# RollerControllerUSB.net
KiCad netlist of a schematic drawn in EAGLE
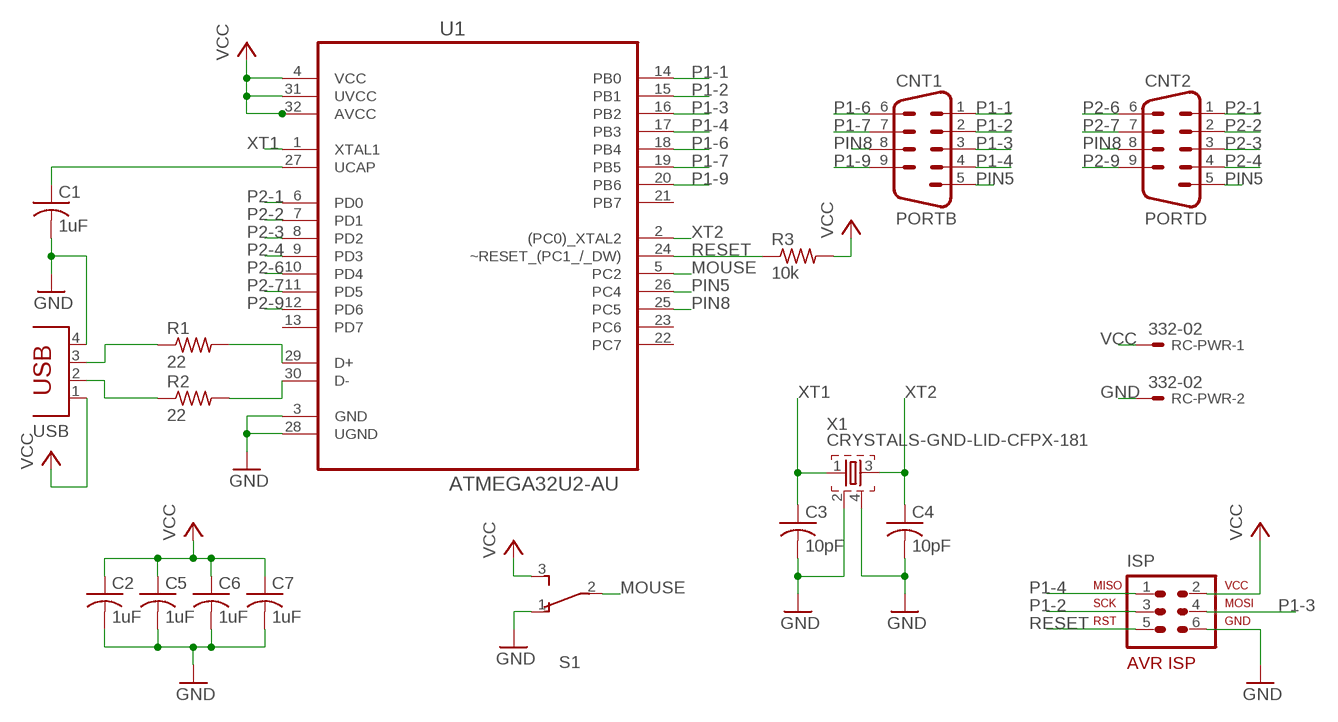
[diagram p0: schematic, sheet 1]

(export (version "E")
  (design (tool "Eeschema 10.0.6"))
  (components
    (comp (ref "C1")
      (value "1uF")
      (footprint "eagle-import:C0603")
      (libsource (lib "eagle-import") (part "C-USC0603"))
    )
    (comp (ref "C2")
      (value "1uF")
      (footprint "eagle-import:C0603")
      (libsource (lib "eagle-import") (part "C-USC0603"))
    )
    (comp (ref "C3")
      (value "10pF")
      (footprint "eagle-import:C0603")
      (libsource (lib "eagle-import") (part "C-USC0603"))
    )
    (comp (ref "C4")
      (value "10pF")
      (footprint "eagle-import:C0603")
      (libsource (lib "eagle-import") (part "C-USC0603"))
    )
    (comp (ref "C5")
      (value "1uF")
      (footprint "eagle-import:C0603")
      (libsource (lib "eagle-import") (part "C-USC0603"))
    )
    (comp (ref "C6")
      (value "1uF")
      (footprint "eagle-import:C0603")
      (libsource (lib "eagle-import") (part "C-USC0603"))
    )
    (comp (ref "C7")
      (value "1uF")
      (footprint "eagle-import:C0603")
      (libsource (lib "eagle-import") (part "C-USC0603"))
    )
    (comp (ref "CNT1")
      (value "PORTB")
      (footprint "eagle-import:M09HP")
      (libsource (lib "eagle-import") (part "M09HP"))
    )
    (comp (ref "CNT2")
      (value "PORTD")
      (footprint "eagle-import:M09HP")
      (libsource (lib "eagle-import") (part "M09HP"))
    )
    (comp (ref "ISP")
      (value "AVR-ISP-6VERT")
      (footprint "eagle-import:AVR-ISP-6")
      (libsource (lib "eagle-import") (part "AVR-ISP-6VERT"))
    )
    (comp (ref "R1")
      (value "22")
      (footprint "eagle-import:R0603")
      (libsource (lib "eagle-import") (part "R-US_R0603"))
    )
    (comp (ref "R2")
      (value "22")
      (footprint "eagle-import:R0603")
      (libsource (lib "eagle-import") (part "R-US_R0603"))
    )
    (comp (ref "R3")
      (value "10k")
      (footprint "eagle-import:R0805")
      (libsource (lib "eagle-import") (part "R-US_R0805"))
    )
    (comp (ref "RC-PWR")
      (value "332-02")
      (footprint "eagle-import:332-02")
      (libsource (lib "eagle-import") (part "332-02"))
    )
    (comp (ref "S1")
      (value "OS102011MA1QN1")
      (footprint "eagle-import:OS102011MA1QN1")
      (libsource (lib "eagle-import") (part "OS102011MA1QN1"))
    )
    (comp (ref "U1")
      (value "ATMEGA32U2-AU")
      (footprint "eagle-import:QFP80P900X900X120-32N")
      (libsource (lib "eagle-import") (part "ATMEGA32U2-AU"))
    )
    (comp (ref "USB")
      (value "PN61729")
      (footprint "eagle-import:PN61729")
      (libsource (lib "eagle-import") (part "PN61729"))
    )
    (comp (ref "X1")
      (value "CRYSTALS-GND-LID-CFPX-181")
      (footprint "eagle-import:2.5X2-4-PAD")
      (libsource (lib "eagle-import") (part "CRYSTALS-GND-LID-CFPX-181"))
    )
  )
  (nets
    (net (code "1") (name "/MOUSE") (class "Default")
      (node (ref "S1") (pin "2") (pinfunction "P_2") (pintype "passive"))
      (node (ref "U1") (pin "5") (pinfunction "PC2_5") (pintype "bidirectional"))
    )
    (net (code "2") (name "/P1-1") (class "Default")
      (node (ref "CNT1") (pin "1") (pinfunction "1_1") (pintype "passive"))
      (node (ref "U1") (pin "14") (pinfunction "PB0_14") (pintype "bidirectional"))
    )
    (net (code "3") (name "/P1-2") (class "Default")
      (node (ref "CNT1") (pin "2") (pinfunction "2_2") (pintype "passive"))
      (node (ref "ISP") (pin "3") (pinfunction "3_3") (pintype "passive"))
      (node (ref "U1") (pin "15") (pinfunction "PB1_15") (pintype "bidirectional"))
    )
    (net (code "4") (name "/P1-3") (class "Default")
      (node (ref "CNT1") (pin "3") (pinfunction "3_3") (pintype "passive"))
      (node (ref "ISP") (pin "4") (pinfunction "4_4") (pintype "passive"))
      (node (ref "U1") (pin "16") (pinfunction "PB2_16") (pintype "bidirectional"))
    )
    (net (code "5") (name "/P1-4") (class "Default")
      (node (ref "CNT1") (pin "4") (pinfunction "4_4") (pintype "passive"))
      (node (ref "ISP") (pin "1") (pinfunction "1_1") (pintype "passive"))
      (node (ref "U1") (pin "17") (pinfunction "PB3_17") (pintype "bidirectional"))
    )
    (net (code "6") (name "/P1-6") (class "Default")
      (node (ref "CNT1") (pin "6") (pinfunction "6_6") (pintype "passive"))
      (node (ref "U1") (pin "18") (pinfunction "PB4_18") (pintype "bidirectional"))
    )
    (net (code "7") (name "/P1-7") (class "Default")
      (node (ref "CNT1") (pin "7") (pinfunction "7_7") (pintype "passive"))
      (node (ref "U1") (pin "19") (pinfunction "PB5_19") (pintype "bidirectional"))
    )
    (net (code "8") (name "/P1-9") (class "Default")
      (node (ref "CNT1") (pin "9") (pinfunction "9_9") (pintype "passive"))
      (node (ref "U1") (pin "20") (pinfunction "PB6_20") (pintype "bidirectional"))
    )
    (net (code "9") (name "/P2-1") (class "Default")
      (node (ref "CNT2") (pin "1") (pinfunction "1_1") (pintype "passive"))
      (node (ref "U1") (pin "6") (pinfunction "PD0_6") (pintype "bidirectional"))
    )
    (net (code "10") (name "/P2-2") (class "Default")
      (node (ref "CNT2") (pin "2") (pinfunction "2_2") (pintype "passive"))
      (node (ref "U1") (pin "7") (pinfunction "PD1_7") (pintype "bidirectional"))
    )
    (net (code "11") (name "/P2-3") (class "Default")
      (node (ref "CNT2") (pin "3") (pinfunction "3_3") (pintype "passive"))
      (node (ref "U1") (pin "8") (pinfunction "PD2_8") (pintype "bidirectional"))
    )
    (net (code "12") (name "/P2-4") (class "Default")
      (node (ref "CNT2") (pin "4") (pinfunction "4_4") (pintype "passive"))
      (node (ref "U1") (pin "9") (pinfunction "PD3_9") (pintype "bidirectional"))
    )
    (net (code "13") (name "/P2-6") (class "Default")
      (node (ref "CNT2") (pin "6") (pinfunction "6_6") (pintype "passive"))
      (node (ref "U1") (pin "10") (pinfunction "PD4_10") (pintype "bidirectional"))
    )
    (net (code "14") (name "/P2-7") (class "Default")
      (node (ref "CNT2") (pin "7") (pinfunction "7_7") (pintype "passive"))
      (node (ref "U1") (pin "11") (pinfunction "PD5_11") (pintype "bidirectional"))
    )
    (net (code "15") (name "/P2-9") (class "Default")
      (node (ref "CNT2") (pin "9") (pinfunction "9_9") (pintype "passive"))
      (node (ref "U1") (pin "12") (pinfunction "PD6_12") (pintype "bidirectional"))
    )
    (net (code "16") (name "/PIN5") (class "Default")
      (node (ref "CNT1") (pin "5") (pinfunction "5_5") (pintype "passive"))
      (node (ref "CNT2") (pin "5") (pinfunction "5_5") (pintype "passive"))
      (node (ref "U1") (pin "26") (pinfunction "PC4_26") (pintype "bidirectional"))
    )
    (net (code "17") (name "/PIN8") (class "Default")
      (node (ref "CNT1") (pin "8") (pinfunction "8_8") (pintype "passive"))
      (node (ref "CNT2") (pin "8") (pinfunction "8_8") (pintype "passive"))
      (node (ref "U1") (pin "25") (pinfunction "PC5_25") (pintype "bidirectional"))
    )
    (net (code "18") (name "/RESET") (class "Default")
      (node (ref "ISP") (pin "5") (pinfunction "5_5") (pintype "passive"))
      (node (ref "R3") (pin "1") (pinfunction "1_1") (pintype "passive"))
      (node (ref "U1") (pin "24") (pinfunction "~{RESET_(PC1_/_DW})_24") (pintype "bidirectional"))
    )
    (net (code "19") (name "/XT1") (class "Default")
      (node (ref "C3") (pin "1") (pinfunction "1_1") (pintype "passive"))
      (node (ref "U1") (pin "1") (pinfunction "XTAL1_1") (pintype "input"))
      (node (ref "X1") (pin "1") (pinfunction "1_1") (pintype "passive"))
    )
    (net (code "20") (name "/XT2") (class "Default")
      (node (ref "C4") (pin "1") (pinfunction "1_1") (pintype "passive"))
      (node (ref "U1") (pin "2") (pinfunction "(PC0)_XTAL2_2") (pintype "bidirectional"))
      (node (ref "X1") (pin "3") (pinfunction "3_3") (pintype "passive"))
    )
    (net (code "21") (name "GND") (class "Default")
      (node (ref "C1") (pin "2") (pinfunction "2_2") (pintype "passive"))
      (node (ref "C2") (pin "2") (pinfunction "2_2") (pintype "passive"))
      (node (ref "C3") (pin "2") (pinfunction "2_2") (pintype "passive"))
      (node (ref "C4") (pin "2") (pinfunction "2_2") (pintype "passive"))
      (node (ref "C5") (pin "2") (pinfunction "2_2") (pintype "passive"))
      (node (ref "C6") (pin "2") (pinfunction "2_2") (pintype "passive"))
      (node (ref "C7") (pin "2") (pinfunction "2_2") (pintype "passive"))
      (node (ref "ISP") (pin "6") (pinfunction "6_6") (pintype "passive"))
      (node (ref "RC-PWR") (pin "2") (pinfunction "S_2") (pintype "passive"))
      (node (ref "S1") (pin "1") (pinfunction "O_1") (pintype "passive"))
      (node (ref "U1") (pin "28") (pinfunction "UGND_28") (pintype "passive"))
      (node (ref "U1") (pin "3") (pinfunction "GND_3") (pintype "passive"))
      (node (ref "USB") (pin "4") (pinfunction "4_4") (pintype "passive"))
      (node (ref "X1") (pin "2") (pinfunction "2_2") (pintype "passive"))
      (node (ref "X1") (pin "4") (pinfunction "4_4") (pintype "passive"))
    )
    (net (code "22") (name "Net-(R1-Pad1)") (class "Default")
      (node (ref "R1") (pin "1") (pinfunction "1_1") (pintype "passive"))
      (node (ref "USB") (pin "3") (pinfunction "3_3") (pintype "passive"))
    )
    (net (code "23") (name "Net-(R2-Pad1)") (class "Default")
      (node (ref "R2") (pin "1") (pinfunction "1_1") (pintype "passive"))
      (node (ref "USB") (pin "2") (pinfunction "2_2") (pintype "passive"))
    )
    (net (code "24") (name "Net-(U1-D+)") (class "Default")
      (node (ref "R1") (pin "2") (pinfunction "2_2") (pintype "passive"))
      (node (ref "U1") (pin "29") (pinfunction "D+_29") (pintype "bidirectional"))
    )
    (net (code "25") (name "Net-(U1-D-)") (class "Default")
      (node (ref "R2") (pin "2") (pinfunction "2_2") (pintype "passive"))
      (node (ref "U1") (pin "30") (pinfunction "D-_30") (pintype "bidirectional"))
    )
    (net (code "26") (name "Net-(U1-UCAP)") (class "Default")
      (node (ref "C1") (pin "1") (pinfunction "1_1") (pintype "passive"))
      (node (ref "U1") (pin "27") (pinfunction "UCAP_27") (pintype "power_in"))
    )
    (net (code "27") (name "VCC") (class "Default")
      (node (ref "C2") (pin "1") (pinfunction "1_1") (pintype "passive"))
      (node (ref "C5") (pin "1") (pinfunction "1_1") (pintype "passive"))
      (node (ref "C6") (pin "1") (pinfunction "1_1") (pintype "passive"))
      (node (ref "C7") (pin "1") (pinfunction "1_1") (pintype "passive"))
      (node (ref "ISP") (pin "2") (pinfunction "2_2") (pintype "passive"))
      (node (ref "R3") (pin "2") (pinfunction "2_2") (pintype "passive"))
      (node (ref "RC-PWR") (pin "1") (pinfunction "S_1") (pintype "passive"))
      (node (ref "S1") (pin "3") (pinfunction "S_3") (pintype "passive"))
      (node (ref "U1") (pin "31") (pinfunction "UVCC_31") (pintype "power_in"))
      (node (ref "U1") (pin "32") (pinfunction "AVCC_32") (pintype "power_in"))
      (node (ref "U1") (pin "4") (pinfunction "VCC_4") (pintype "power_in"))
      (node (ref "USB") (pin "1") (pinfunction "1_1") (pintype "passive"))
    )
    (net (code "28") (name "unconnected-(U1-PB7-Pad21)") (class "Default")
      (node (ref "U1") (pin "21") (pinfunction "PB7_21") (pintype "bidirectional"))
    )
    (net (code "29") (name "unconnected-(U1-PC6-Pad23)") (class "Default")
      (node (ref "U1") (pin "23") (pinfunction "PC6_23") (pintype "bidirectional"))
    )
    (net (code "30") (name "unconnected-(U1-PC7-Pad22)") (class "Default")
      (node (ref "U1") (pin "22") (pinfunction "PC7_22") (pintype "bidirectional"))
    )
    (net (code "31") (name "unconnected-(U1-PD7-Pad13)") (class "Default")
      (node (ref "U1") (pin "13") (pinfunction "PD7_13") (pintype "bidirectional"))
    )
  )
)
